# Lamps.net
KiCad netlist of a schematic drawn in Altium Designer
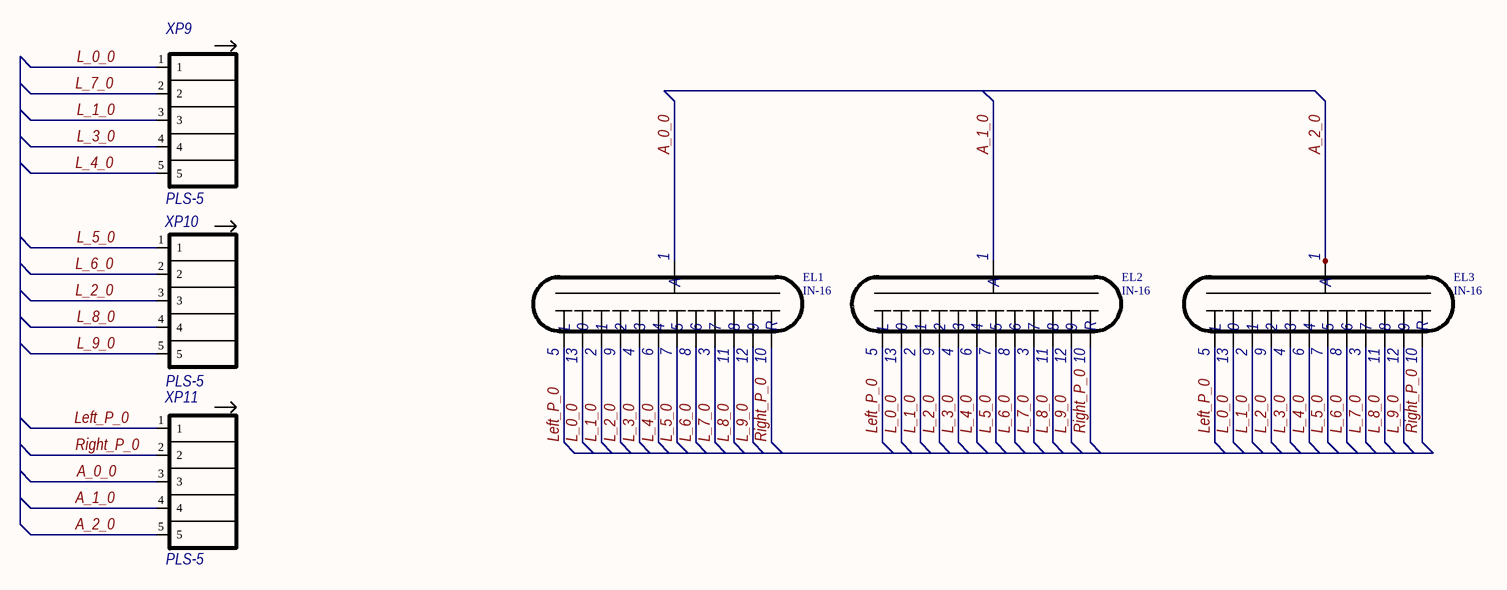
[diagram p0: Lamps.SchDoc]

(export (version "E")
  (design (tool "Eeschema 10.0.6"))
  (components
    (comp (ref "EL1") (value "IN-16") (footprint "IN-16") (libsource (lib "sobol_lib") (part "IN-16")))
    (comp (ref "EL2") (value "IN-16") (footprint "IN-16") (libsource (lib "sobol_lib") (part "IN-16")))
    (comp (ref "EL3") (value "IN-16") (footprint "IN-16") (libsource (lib "sobol_lib") (part "IN-16")))
    (comp (ref "XP9") (value "PLS-5") (footprint "PLS-5") (libsource (lib "sobol_lib") (part "PLS-5")))
    (comp (ref "XP10") (value "PLS-5") (footprint "PLS-5") (libsource (lib "sobol_lib") (part "PLS-5")))
    (comp (ref "XP11") (value "PLS-5") (footprint "PLS-5") (libsource (lib "sobol_lib") (part "PLS-5")))
  )
  (nets
    (net (code "1") (name "/A_0_0") (class "Default")
      (node (ref "EL1") (pin "1") (pinfunction "A_1") (pintype "passive"))
      (node (ref "XP11") (pin "3") (pinfunction "3_3") (pintype "passive"))
    )
    (net (code "2") (name "/A_1_0") (class "Default")
      (node (ref "EL2") (pin "1") (pinfunction "A_1") (pintype "passive"))
      (node (ref "XP11") (pin "4") (pinfunction "4_4") (pintype "passive"))
    )
    (net (code "3") (name "/A_2_0") (class "Default")
      (node (ref "EL3") (pin "1") (pinfunction "A_1") (pintype "passive"))
      (node (ref "XP11") (pin "5") (pinfunction "5_5") (pintype "passive"))
    )
    (net (code "4") (name "/L_0_0") (class "Default")
      (node (ref "EL1") (pin "13") (pinfunction "0_13") (pintype "passive"))
      (node (ref "EL2") (pin "13") (pinfunction "0_13") (pintype "passive"))
      (node (ref "EL3") (pin "13") (pinfunction "0_13") (pintype "passive"))
      (node (ref "XP9") (pin "1") (pinfunction "1_1") (pintype "passive"))
    )
    (net (code "5") (name "/L_1_0") (class "Default")
      (node (ref "EL1") (pin "2") (pinfunction "1_2") (pintype "passive"))
      (node (ref "EL2") (pin "2") (pinfunction "1_2") (pintype "passive"))
      (node (ref "EL3") (pin "2") (pinfunction "1_2") (pintype "passive"))
      (node (ref "XP9") (pin "3") (pinfunction "3_3") (pintype "passive"))
    )
    (net (code "6") (name "/L_2_0") (class "Default")
      (node (ref "EL1") (pin "9") (pinfunction "2_9") (pintype "passive"))
      (node (ref "EL2") (pin "9") (pinfunction "2_9") (pintype "passive"))
      (node (ref "EL3") (pin "9") (pinfunction "2_9") (pintype "passive"))
      (node (ref "XP10") (pin "3") (pinfunction "3_3") (pintype "passive"))
    )
    (net (code "7") (name "/L_3_0") (class "Default")
      (node (ref "EL1") (pin "4") (pinfunction "3_4") (pintype "passive"))
      (node (ref "EL2") (pin "4") (pinfunction "3_4") (pintype "passive"))
      (node (ref "EL3") (pin "4") (pinfunction "3_4") (pintype "passive"))
      (node (ref "XP9") (pin "4") (pinfunction "4_4") (pintype "passive"))
    )
    (net (code "8") (name "/L_4_0") (class "Default")
      (node (ref "EL1") (pin "6") (pinfunction "4_6") (pintype "passive"))
      (node (ref "EL2") (pin "6") (pinfunction "4_6") (pintype "passive"))
      (node (ref "EL3") (pin "6") (pinfunction "4_6") (pintype "passive"))
      (node (ref "XP9") (pin "5") (pinfunction "5_5") (pintype "passive"))
    )
    (net (code "9") (name "/L_5_0") (class "Default")
      (node (ref "EL1") (pin "7") (pinfunction "5_7") (pintype "passive"))
      (node (ref "EL2") (pin "7") (pinfunction "5_7") (pintype "passive"))
      (node (ref "EL3") (pin "7") (pinfunction "5_7") (pintype "passive"))
      (node (ref "XP10") (pin "1") (pinfunction "1_1") (pintype "passive"))
    )
    (net (code "10") (name "/L_6_0") (class "Default")
      (node (ref "EL1") (pin "8") (pinfunction "6_8") (pintype "passive"))
      (node (ref "EL2") (pin "8") (pinfunction "6_8") (pintype "passive"))
      (node (ref "EL3") (pin "8") (pinfunction "6_8") (pintype "passive"))
      (node (ref "XP10") (pin "2") (pinfunction "2_2") (pintype "passive"))
    )
    (net (code "11") (name "/L_7_0") (class "Default")
      (node (ref "EL1") (pin "3") (pinfunction "7_3") (pintype "passive"))
      (node (ref "EL2") (pin "3") (pinfunction "7_3") (pintype "passive"))
      (node (ref "EL3") (pin "3") (pinfunction "7_3") (pintype "passive"))
      (node (ref "XP9") (pin "2") (pinfunction "2_2") (pintype "passive"))
    )
    (net (code "12") (name "/L_8_0") (class "Default")
      (node (ref "EL1") (pin "11") (pinfunction "8_11") (pintype "passive"))
      (node (ref "EL2") (pin "11") (pinfunction "8_11") (pintype "passive"))
      (node (ref "EL3") (pin "11") (pinfunction "8_11") (pintype "passive"))
      (node (ref "XP10") (pin "4") (pinfunction "4_4") (pintype "passive"))
    )
    (net (code "13") (name "/L_9_0") (class "Default")
      (node (ref "EL1") (pin "12") (pinfunction "9_12") (pintype "passive"))
      (node (ref "EL2") (pin "12") (pinfunction "9_12") (pintype "passive"))
      (node (ref "EL3") (pin "12") (pinfunction "9_12") (pintype "passive"))
      (node (ref "XP10") (pin "5") (pinfunction "5_5") (pintype "passive"))
    )
    (net (code "14") (name "/Left_P_0") (class "Default")
      (node (ref "EL1") (pin "5") (pinfunction "L_5") (pintype "passive"))
      (node (ref "EL2") (pin "5") (pinfunction "L_5") (pintype "passive"))
      (node (ref "EL3") (pin "5") (pinfunction "L_5") (pintype "passive"))
      (node (ref "XP11") (pin "1") (pinfunction "1_1") (pintype "passive"))
    )
    (net (code "15") (name "/Right_P_0") (class "Default")
      (node (ref "EL1") (pin "10") (pinfunction "R_10") (pintype "passive"))
      (node (ref "EL2") (pin "10") (pinfunction "R_10") (pintype "passive"))
      (node (ref "EL3") (pin "10") (pinfunction "R_10") (pintype "passive"))
      (node (ref "XP11") (pin "2") (pinfunction "2_2") (pintype "passive"))
    )
  )
)
